# InputChannel.net
KiCad netlist of a schematic drawn in EAGLE
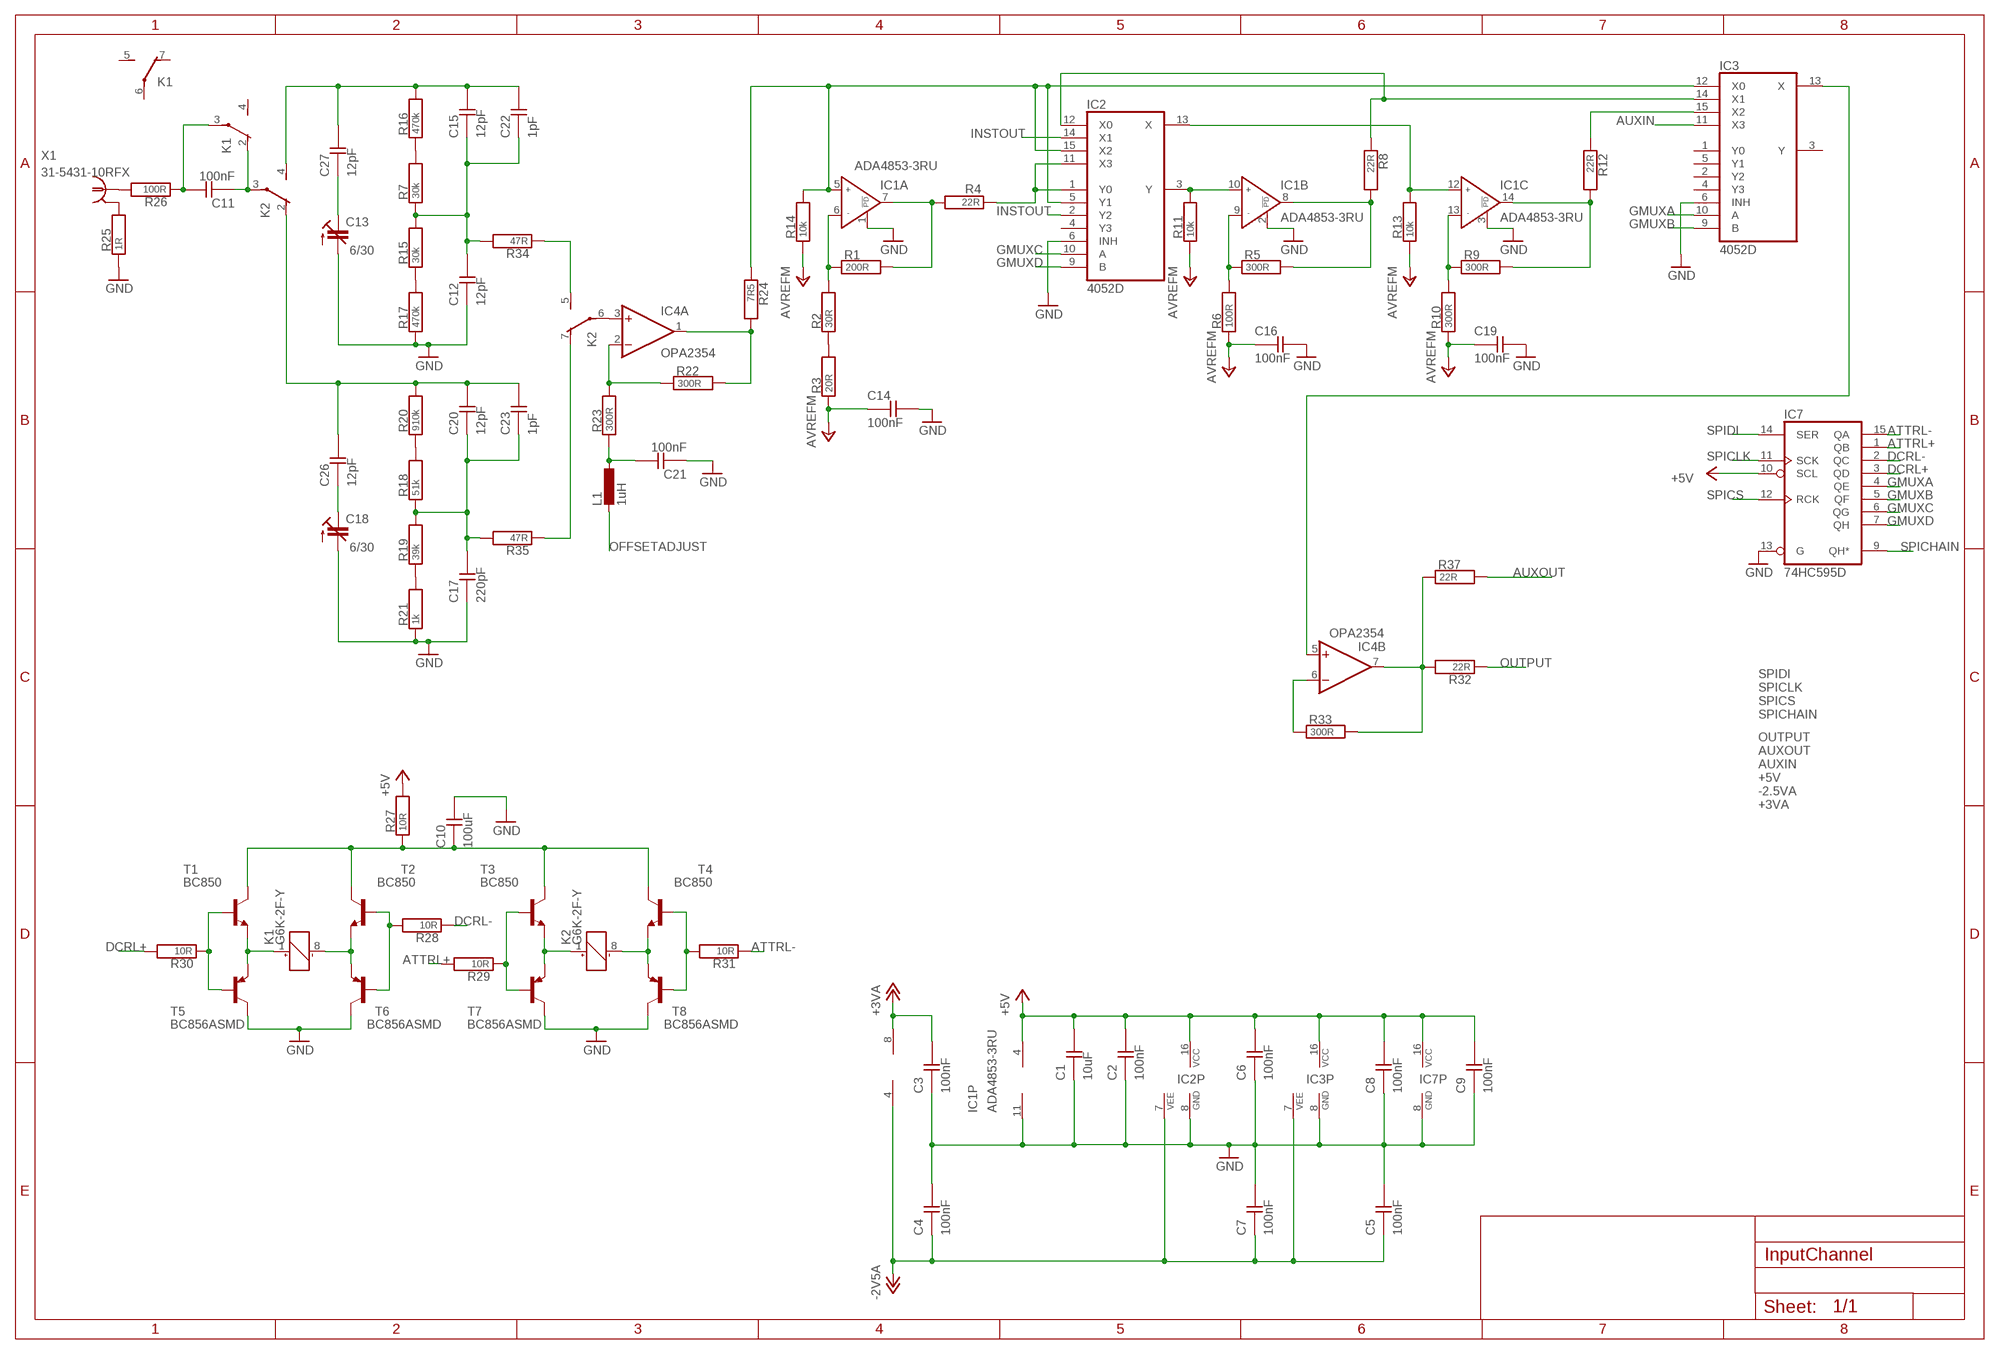
[diagram p0: schematic, sheet 1]

(export (version "E")
  (design (tool "Eeschema 10.0.6"))
  (components
    (comp (ref "C1")
      (value "10uF")
      (footprint "eagle-import:0603")
      (libsource (lib "eagle-import") (part "CAPC0603"))
    )
    (comp (ref "C2")
      (value "100nF")
      (footprint "eagle-import:0603")
      (libsource (lib "eagle-import") (part "CAPC0603"))
    )
    (comp (ref "C3")
      (value "100nF")
      (footprint "eagle-import:0603")
      (libsource (lib "eagle-import") (part "CAPC0603"))
    )
    (comp (ref "C4")
      (value "100nF")
      (footprint "eagle-import:0402")
      (libsource (lib "eagle-import") (part "CAPC0402"))
    )
    (comp (ref "C5")
      (value "100nF")
      (footprint "eagle-import:0603")
      (libsource (lib "eagle-import") (part "CAPC0603"))
    )
    (comp (ref "C6")
      (value "100nF")
      (footprint "eagle-import:0603")
      (libsource (lib "eagle-import") (part "CAPC0603"))
    )
    (comp (ref "C7")
      (value "100nF")
      (footprint "eagle-import:0603")
      (libsource (lib "eagle-import") (part "CAPC0603"))
    )
    (comp (ref "C8")
      (value "100nF")
      (footprint "eagle-import:0603")
      (libsource (lib "eagle-import") (part "CAPC0603"))
    )
    (comp (ref "C9")
      (value "100nF")
      (footprint "eagle-import:0603")
      (libsource (lib "eagle-import") (part "CAPC0603"))
    )
    (comp (ref "C10")
      (value "100uF")
      (footprint "eagle-import:1206")
      (libsource (lib "eagle-import") (part "CAPC1206"))
    )
    (comp (ref "C11")
      (value "100nF")
      (footprint "eagle-import:0603")
      (libsource (lib "eagle-import") (part "CAPC0603"))
    )
    (comp (ref "C12")
      (value "12pF")
      (footprint "eagle-import:0603")
      (libsource (lib "eagle-import") (part "CAPC0603"))
    )
    (comp (ref "C13")
      (value "6/30")
      (footprint "eagle-import:CTRIMTZBX4")
      (libsource (lib "eagle-import") (part "C-TRIMMTZBX4"))
    )
    (comp (ref "C14")
      (value "100nF")
      (footprint "eagle-import:0402")
      (libsource (lib "eagle-import") (part "CAPC0402"))
    )
    (comp (ref "C15")
      (value "12pF")
      (footprint "eagle-import:0603")
      (libsource (lib "eagle-import") (part "CAPC0603"))
    )
    (comp (ref "C16")
      (value "100nF")
      (footprint "eagle-import:0402")
      (libsource (lib "eagle-import") (part "CAPC0402"))
    )
    (comp (ref "C17")
      (value "220pF")
      (footprint "eagle-import:0603")
      (libsource (lib "eagle-import") (part "CAPC0603"))
    )
    (comp (ref "C18")
      (value "6/30")
      (footprint "eagle-import:CTRIMTZBX4")
      (libsource (lib "eagle-import") (part "C-TRIMMTZBX4"))
    )
    (comp (ref "C19")
      (value "100nF")
      (footprint "eagle-import:0402")
      (libsource (lib "eagle-import") (part "CAPC0402"))
    )
    (comp (ref "C20")
      (value "12pF")
      (footprint "eagle-import:0603")
      (libsource (lib "eagle-import") (part "CAPC0603"))
    )
    (comp (ref "C21")
      (value "100nF")
      (footprint "eagle-import:0402")
      (libsource (lib "eagle-import") (part "CAPC0402"))
    )
    (comp (ref "C22")
      (value "1pF")
      (footprint "eagle-import:0603")
      (libsource (lib "eagle-import") (part "CAPC0603"))
    )
    (comp (ref "C23")
      (value "1pF")
      (footprint "eagle-import:0603")
      (libsource (lib "eagle-import") (part "CAPC0603"))
    )
    (comp (ref "C26")
      (value "12pF")
      (footprint "eagle-import:0603")
      (libsource (lib "eagle-import") (part "CAPC0603"))
    )
    (comp (ref "C27")
      (value "12pF")
      (footprint "eagle-import:0603")
      (libsource (lib "eagle-import") (part "CAPC0603"))
    )
    (comp (ref "IC1")
      (value "ADA4853-3RU")
      (footprint "eagle-import:SO14")
      (libsource (lib "eagle-import") (part "ADA4853-3RU"))
    )
    (comp (ref "IC2")
      (value "4052D")
      (footprint "eagle-import:SO16")
      (libsource (lib "eagle-import") (part "4052D"))
    )
    (comp (ref "IC3")
      (value "4052D")
      (footprint "eagle-import:SO16")
      (libsource (lib "eagle-import") (part "4052D"))
    )
    (comp (ref "IC4")
      (value "OPA2354")
      (footprint "eagle-import:MSOP08")
      (libsource (lib "eagle-import") (part "AD8682RM"))
    )
    (comp (ref "IC7")
      (value "74HC595D")
      (footprint "eagle-import:SO16")
      (libsource (lib "eagle-import") (part "74595DHC"))
    )
    (comp (ref "K1")
      (value "G6K-2F-Y")
      (footprint "eagle-import:G6K-2F-Y")
      (fields (field (name "MF") "OMRON COMPONENTS USA") (field (name "MPN") "G6K-2F-Y DC3"))
      (libsource (lib "eagle-import") (part "G6K-2F-Y"))
    )
    (comp (ref "K2")
      (value "G6K-2F-Y")
      (footprint "eagle-import:G6K-2F-Y")
      (fields (field (name "MF") "OMRON COMPONENTS USA") (field (name "MPN") "G6K-2F-Y DC3"))
      (libsource (lib "eagle-import") (part "G6K-2F-Y"))
    )
    (comp (ref "L1")
      (value "1uH")
      (footprint "eagle-import:L3216C")
      (libsource (lib "eagle-import") (part "L-EUL3216C"))
    )
    (comp (ref "R1")
      (value "200R")
      (footprint "eagle-import:0603")
      (libsource (lib "eagle-import") (part "RESR0603"))
    )
    (comp (ref "R2")
      (value "30R")
      (footprint "eagle-import:0603")
      (libsource (lib "eagle-import") (part "RESR0603"))
    )
    (comp (ref "R3")
      (value "20R")
      (footprint "eagle-import:0603")
      (libsource (lib "eagle-import") (part "RESR0603"))
    )
    (comp (ref "R4")
      (value "22R")
      (footprint "eagle-import:0603")
      (libsource (lib "eagle-import") (part "RESR0603"))
    )
    (comp (ref "R5")
      (value "300R")
      (footprint "eagle-import:0603")
      (libsource (lib "eagle-import") (part "RESR0603"))
    )
    (comp (ref "R6")
      (value "100R")
      (footprint "eagle-import:0603")
      (libsource (lib "eagle-import") (part "RESR0603"))
    )
    (comp (ref "R7")
      (value "30k")
      (footprint "eagle-import:0603")
      (libsource (lib "eagle-import") (part "RESR0603"))
    )
    (comp (ref "R8")
      (value "22R")
      (footprint "eagle-import:0603")
      (libsource (lib "eagle-import") (part "RESR0603"))
    )
    (comp (ref "R9")
      (value "300R")
      (footprint "eagle-import:0603")
      (libsource (lib "eagle-import") (part "RESR0603"))
    )
    (comp (ref "R10")
      (value "300R")
      (footprint "eagle-import:0603")
      (libsource (lib "eagle-import") (part "RESR0603"))
    )
    (comp (ref "R11")
      (value "10k")
      (footprint "eagle-import:0603")
      (libsource (lib "eagle-import") (part "RESR0603"))
    )
    (comp (ref "R12")
      (value "22R")
      (footprint "eagle-import:0603")
      (libsource (lib "eagle-import") (part "RESR0603"))
    )
    (comp (ref "R13")
      (value "10k")
      (footprint "eagle-import:0603")
      (libsource (lib "eagle-import") (part "RESR0603"))
    )
    (comp (ref "R14")
      (value "10k")
      (footprint "eagle-import:0603")
      (libsource (lib "eagle-import") (part "RESR0603"))
    )
    (comp (ref "R15")
      (value "30k")
      (footprint "eagle-import:0603")
      (libsource (lib "eagle-import") (part "RESR0603"))
    )
    (comp (ref "R16")
      (value "470k")
      (footprint "eagle-import:0603")
      (libsource (lib "eagle-import") (part "RESR0603"))
    )
    (comp (ref "R17")
      (value "470k")
      (footprint "eagle-import:0603")
      (libsource (lib "eagle-import") (part "RESR0603"))
    )
    (comp (ref "R18")
      (value "51k")
      (footprint "eagle-import:0603")
      (libsource (lib "eagle-import") (part "RESR0603"))
    )
    (comp (ref "R19")
      (value "39k")
      (footprint "eagle-import:0603")
      (libsource (lib "eagle-import") (part "RESR0603"))
    )
    (comp (ref "R20")
      (value "910k")
      (footprint "eagle-import:0603")
      (libsource (lib "eagle-import") (part "RESR0603"))
    )
    (comp (ref "R21")
      (value "1k")
      (footprint "eagle-import:0603")
      (libsource (lib "eagle-import") (part "RESR0603"))
    )
    (comp (ref "R22")
      (value "300R")
      (footprint "eagle-import:0603")
      (libsource (lib "eagle-import") (part "RESR0603"))
    )
    (comp (ref "R23")
      (value "300R")
      (footprint "eagle-import:0603")
      (libsource (lib "eagle-import") (part "RESR0603"))
    )
    (comp (ref "R24")
      (value "7R5")
      (footprint "eagle-import:0603")
      (libsource (lib "eagle-import") (part "RESR0603"))
    )
    (comp (ref "R25")
      (value "1R")
      (footprint "eagle-import:0603")
      (libsource (lib "eagle-import") (part "RESR0603"))
    )
    (comp (ref "R26")
      (value "100R")
      (footprint "eagle-import:0603")
      (libsource (lib "eagle-import") (part "RESR0603"))
    )
    (comp (ref "R27")
      (value "10R")
      (footprint "eagle-import:0603")
      (libsource (lib "eagle-import") (part "RESR0603"))
    )
    (comp (ref "R28")
      (value "10R")
      (footprint "eagle-import:0603")
      (libsource (lib "eagle-import") (part "RESR0603"))
    )
    (comp (ref "R29")
      (value "10R")
      (footprint "eagle-import:0603")
      (libsource (lib "eagle-import") (part "RESR0603"))
    )
    (comp (ref "R30")
      (value "10R")
      (footprint "eagle-import:0603")
      (libsource (lib "eagle-import") (part "RESR0603"))
    )
    (comp (ref "R31")
      (value "10R")
      (footprint "eagle-import:0603")
      (libsource (lib "eagle-import") (part "RESR0603"))
    )
    (comp (ref "R32")
      (value "22R")
      (footprint "eagle-import:0603")
      (libsource (lib "eagle-import") (part "RESR0603"))
    )
    (comp (ref "R33")
      (value "300R")
      (footprint "eagle-import:0603")
      (libsource (lib "eagle-import") (part "RESR0603"))
    )
    (comp (ref "R34")
      (value "47R")
      (footprint "eagle-import:0603")
      (libsource (lib "eagle-import") (part "RESR0603"))
    )
    (comp (ref "R35")
      (value "47R")
      (footprint "eagle-import:0603")
      (libsource (lib "eagle-import") (part "RESR0603"))
    )
    (comp (ref "R37")
      (value "22R")
      (footprint "eagle-import:0603")
      (libsource (lib "eagle-import") (part "RESR0603"))
    )
    (comp (ref "T1")
      (value "BC850")
      (footprint "eagle-import:SOT23")
      (libsource (lib "eagle-import") (part "BC850"))
    )
    (comp (ref "T2")
      (value "BC850")
      (footprint "eagle-import:SOT23")
      (libsource (lib "eagle-import") (part "BC850"))
    )
    (comp (ref "T3")
      (value "BC850")
      (footprint "eagle-import:SOT23")
      (libsource (lib "eagle-import") (part "BC850"))
    )
    (comp (ref "T4")
      (value "BC850")
      (footprint "eagle-import:SOT23")
      (libsource (lib "eagle-import") (part "BC850"))
    )
    (comp (ref "T5")
      (value "BC856ASMD")
      (footprint "eagle-import:SOT23-BEC")
      (libsource (lib "eagle-import") (part "BC856SMDA"))
    )
    (comp (ref "T6")
      (value "BC856ASMD")
      (footprint "eagle-import:SOT23-BEC")
      (libsource (lib "eagle-import") (part "BC856SMDA"))
    )
    (comp (ref "T7")
      (value "BC856ASMD")
      (footprint "eagle-import:SOT23-BEC")
      (libsource (lib "eagle-import") (part "BC856SMDA"))
    )
    (comp (ref "T8")
      (value "BC856ASMD")
      (footprint "eagle-import:SOT23-BEC")
      (libsource (lib "eagle-import") (part "BC856SMDA"))
    )
    (comp (ref "X1")
      (value "31-5431-10RFX")
      (footprint "eagle-import:AMP_227161")
      (libsource (lib "eagle-import") (part "?227161-8"))
    )
  )
  (nets
    (net (code "1") (name "+3VA") (class "Default")
      (node (ref "C3") (pin "2") (pinfunction "2_2") (pintype "passive"))
      (node (ref "IC4") (pin "8") (pinfunction "V+_8") (pintype "power_in"))
    )
    (net (code "2") (name "+5V") (class "Default")
      (node (ref "C1") (pin "2") (pinfunction "2_2") (pintype "passive"))
      (node (ref "C2") (pin "2") (pinfunction "2_2") (pintype "passive"))
      (node (ref "C6") (pin "2") (pinfunction "2_2") (pintype "passive"))
      (node (ref "C8") (pin "2") (pinfunction "2_2") (pintype "passive"))
      (node (ref "C9") (pin "2") (pinfunction "2_2") (pintype "passive"))
      (node (ref "IC1") (pin "4") (pinfunction "V+_4") (pintype "power_in"))
      (node (ref "IC2") (pin "16") (pinfunction "VCC_16") (pintype "power_in"))
      (node (ref "IC3") (pin "16") (pinfunction "VCC_16") (pintype "power_in"))
      (node (ref "IC7") (pin "10") (pinfunction "SCL_10") (pintype "input"))
      (node (ref "IC7") (pin "16") (pinfunction "VCC_16") (pintype "power_in"))
      (node (ref "R27") (pin "2") (pinfunction "P$2_2") (pintype "bidirectional"))
    )
    (net (code "3") (name "-2V5A") (class "Default")
      (node (ref "C4") (pin "1") (pinfunction "1_1") (pintype "passive"))
      (node (ref "C5") (pin "1") (pinfunction "1_1") (pintype "passive"))
      (node (ref "C7") (pin "1") (pinfunction "1_1") (pintype "passive"))
      (node (ref "IC2") (pin "7") (pinfunction "VEE_7") (pintype "power_in"))
      (node (ref "IC3") (pin "7") (pinfunction "VEE_7") (pintype "power_in"))
      (node (ref "IC4") (pin "4") (pinfunction "V-_4") (pintype "power_in"))
    )
    (net (code "4") (name "/ATTRL+") (class "Default")
      (node (ref "IC7") (pin "1") (pinfunction "QB_1") (pintype "tri_state"))
      (node (ref "R29") (pin "2") (pinfunction "P$2_2") (pintype "bidirectional"))
    )
    (net (code "5") (name "/ATTRL-") (class "Default")
      (node (ref "IC7") (pin "15") (pinfunction "QA_15") (pintype "tri_state"))
      (node (ref "R31") (pin "1") (pinfunction "P$1_1") (pintype "bidirectional"))
    )
    (net (code "6") (name "/AUXIN") (class "Default")
      (node (ref "IC3") (pin "11") (pinfunction "X3_11") (pintype "bidirectional"))
    )
    (net (code "7") (name "/AUXOUT") (class "Default")
      (node (ref "R37") (pin "2") (pinfunction "P$2_2") (pintype "bidirectional"))
    )
    (net (code "8") (name "/DCRL+") (class "Default")
      (node (ref "IC7") (pin "3") (pinfunction "QD_3") (pintype "tri_state"))
      (node (ref "R30") (pin "2") (pinfunction "P$2_2") (pintype "bidirectional"))
    )
    (net (code "9") (name "/DCRL-") (class "Default")
      (node (ref "IC7") (pin "2") (pinfunction "QC_2") (pintype "tri_state"))
      (node (ref "R28") (pin "1") (pinfunction "P$1_1") (pintype "bidirectional"))
    )
    (net (code "10") (name "/GMUXA") (class "Default")
      (node (ref "IC3") (pin "10") (pinfunction "A_10") (pintype "input"))
      (node (ref "IC7") (pin "4") (pinfunction "QE_4") (pintype "tri_state"))
    )
    (net (code "11") (name "/GMUXB") (class "Default")
      (node (ref "IC3") (pin "9") (pinfunction "B_9") (pintype "input"))
      (node (ref "IC7") (pin "5") (pinfunction "QF_5") (pintype "tri_state"))
    )
    (net (code "12") (name "/GMUXC") (class "Default")
      (node (ref "IC2") (pin "10") (pinfunction "A_10") (pintype "input"))
      (node (ref "IC7") (pin "6") (pinfunction "QG_6") (pintype "tri_state"))
    )
    (net (code "13") (name "/GMUXD") (class "Default")
      (node (ref "IC2") (pin "9") (pinfunction "B_9") (pintype "input"))
      (node (ref "IC7") (pin "7") (pinfunction "QH_7") (pintype "tri_state"))
    )
    (net (code "14") (name "/INSTOUT") (class "Default")
      (node (ref "IC2") (pin "14") (pinfunction "X1_14") (pintype "bidirectional"))
      (node (ref "IC2") (pin "2") (pinfunction "Y2_2") (pintype "bidirectional"))
    )
    (net (code "15") (name "/OFFSETADJUST") (class "Default")
      (node (ref "L1") (pin "2") (pinfunction "2_2") (pintype "passive"))
    )
    (net (code "16") (name "/OUTPUT") (class "Default")
      (node (ref "R32") (pin "1") (pinfunction "P$1_1") (pintype "bidirectional"))
    )
    (net (code "17") (name "/SPICHAIN") (class "Default")
      (node (ref "IC7") (pin "9") (pinfunction "QH*_9") (pintype "tri_state"))
    )
    (net (code "18") (name "/SPICLK") (class "Default")
      (node (ref "IC7") (pin "11") (pinfunction "SCK_11") (pintype "input"))
    )
    (net (code "19") (name "/SPICS") (class "Default")
      (node (ref "IC7") (pin "12") (pinfunction "RCK_12") (pintype "input"))
    )
    (net (code "20") (name "/SPIDI") (class "Default")
      (node (ref "IC7") (pin "14") (pinfunction "SER_14") (pintype "input"))
    )
    (net (code "21") (name "AVREFM") (class "Default")
      (node (ref "C14") (pin "1") (pinfunction "1_1") (pintype "passive"))
      (node (ref "C16") (pin "1") (pinfunction "1_1") (pintype "passive"))
      (node (ref "C19") (pin "1") (pinfunction "1_1") (pintype "passive"))
      (node (ref "R10") (pin "1") (pinfunction "P$1_1") (pintype "bidirectional"))
      (node (ref "R11") (pin "1") (pinfunction "P$1_1") (pintype "bidirectional"))
      (node (ref "R13") (pin "1") (pinfunction "P$1_1") (pintype "bidirectional"))
      (node (ref "R14") (pin "1") (pinfunction "P$1_1") (pintype "bidirectional"))
      (node (ref "R3") (pin "1") (pinfunction "P$1_1") (pintype "bidirectional"))
      (node (ref "R6") (pin "1") (pinfunction "P$1_1") (pintype "bidirectional"))
    )
    (net (code "22") (name "GND") (class "Default")
      (node (ref "C1") (pin "1") (pinfunction "1_1") (pintype "passive"))
      (node (ref "C10") (pin "2") (pinfunction "2_2") (pintype "passive"))
      (node (ref "C12") (pin "1") (pinfunction "1_1") (pintype "passive"))
      (node (ref "C13") (pin "2") (pinfunction "A_2") (pintype "passive"))
      (node (ref "C14") (pin "2") (pinfunction "2_2") (pintype "passive"))
      (node (ref "C16") (pin "2") (pinfunction "2_2") (pintype "passive"))
      (node (ref "C17") (pin "1") (pinfunction "1_1") (pintype "passive"))
      (node (ref "C18") (pin "2") (pinfunction "A_2") (pintype "passive"))
      (node (ref "C19") (pin "2") (pinfunction "2_2") (pintype "passive"))
      (node (ref "C2") (pin "1") (pinfunction "1_1") (pintype "passive"))
      (node (ref "C21") (pin "1") (pinfunction "1_1") (pintype "passive"))
      (node (ref "C3") (pin "1") (pinfunction "1_1") (pintype "passive"))
      (node (ref "C4") (pin "2") (pinfunction "2_2") (pintype "passive"))
      (node (ref "C5") (pin "2") (pinfunction "2_2") (pintype "passive"))
      (node (ref "C6") (pin "1") (pinfunction "1_1") (pintype "passive"))
      (node (ref "C7") (pin "2") (pinfunction "2_2") (pintype "passive"))
      (node (ref "C8") (pin "1") (pinfunction "1_1") (pintype "passive"))
      (node (ref "C9") (pin "1") (pinfunction "1_1") (pintype "passive"))
      (node (ref "IC1") (pin "1") (pinfunction "~{POWERDOWN}_1") (pintype "passive"))
      (node (ref "IC1") (pin "11") (pinfunction "V-_11") (pintype "power_in"))
      (node (ref "IC1") (pin "2") (pinfunction "~{POWERDOWN}_2") (pintype "passive"))
      (node (ref "IC1") (pin "3") (pinfunction "~{POWERDOWN}_3") (pintype "passive"))
      (node (ref "IC2") (pin "6") (pinfunction "INH_6") (pintype "input"))
      (node (ref "IC2") (pin "8") (pinfunction "GND_8") (pintype "power_in"))
      (node (ref "IC3") (pin "6") (pinfunction "INH_6") (pintype "input"))
      (node (ref "IC3") (pin "8") (pinfunction "GND_8") (pintype "power_in"))
      (node (ref "IC7") (pin "13") (pinfunction "G_13") (pintype "input"))
      (node (ref "IC7") (pin "8") (pinfunction "GND_8") (pintype "power_in"))
      (node (ref "R17") (pin "1") (pinfunction "P$1_1") (pintype "bidirectional"))
      (node (ref "R21") (pin "1") (pinfunction "P$1_1") (pintype "bidirectional"))
      (node (ref "R25") (pin "1") (pinfunction "P$1_1") (pintype "bidirectional"))
      (node (ref "T5") (pin "C") (pinfunction "C_C") (pintype "passive"))
      (node (ref "T6") (pin "C") (pinfunction "C_C") (pintype "passive"))
      (node (ref "T7") (pin "C") (pinfunction "C_C") (pintype "passive"))
      (node (ref "T8") (pin "C") (pinfunction "C_C") (pintype "passive"))
    )
    (net (code "23") (name "Net-(C13-E)") (class "Default")
      (node (ref "C13") (pin "1") (pinfunction "E_1") (pintype "passive"))
      (node (ref "C27") (pin "1") (pinfunction "1_1") (pintype "passive"))
    )
    (net (code "24") (name "Net-(C18-E)") (class "Default")
      (node (ref "C18") (pin "1") (pinfunction "E_1") (pintype "passive"))
      (node (ref "C26") (pin "1") (pinfunction "1_1") (pintype "passive"))
    )
    (net (code "25") (name "Net-(IC1A-IN+)") (class "Default")
      (node (ref "IC1") (pin "5") (pinfunction "IN+_5") (pintype "input"))
      (node (ref "IC2") (pin "15") (pinfunction "X2_15") (pintype "bidirectional"))
      (node (ref "IC2") (pin "5") (pinfunction "Y1_5") (pintype "bidirectional"))
      (node (ref "IC3") (pin "12") (pinfunction "X0_12") (pintype "bidirectional"))
      (node (ref "R14") (pin "2") (pinfunction "P$2_2") (pintype "bidirectional"))
      (node (ref "R24") (pin "1") (pinfunction "P$1_1") (pintype "bidirectional"))
    )
    (net (code "26") (name "Net-(IC1A-IN-)") (class "Default")
      (node (ref "IC1") (pin "6") (pinfunction "IN-_6") (pintype "input"))
      (node (ref "R1") (pin "1") (pinfunction "P$1_1") (pintype "bidirectional"))
      (node (ref "R2") (pin "2") (pinfunction "P$2_2") (pintype "bidirectional"))
    )
    (net (code "27") (name "Net-(IC1A-OUT)") (class "Default")
      (node (ref "IC1") (pin "7") (pinfunction "OUT_7") (pintype "output"))
      (node (ref "R1") (pin "2") (pinfunction "P$2_2") (pintype "bidirectional"))
      (node (ref "R4") (pin "2") (pinfunction "P$2_2") (pintype "bidirectional"))
    )
    (net (code "28") (name "Net-(IC1B-IN+)") (class "Default")
      (node (ref "IC1") (pin "10") (pinfunction "IN+_10") (pintype "input"))
      (node (ref "IC2") (pin "3") (pinfunction "Y_3") (pintype "bidirectional"))
      (node (ref "R11") (pin "2") (pinfunction "P$2_2") (pintype "bidirectional"))
    )
    (net (code "29") (name "Net-(IC1B-IN-)") (class "Default")
      (node (ref "IC1") (pin "9") (pinfunction "IN-_9") (pintype "input"))
      (node (ref "R5") (pin "1") (pinfunction "P$1_1") (pintype "bidirectional"))
      (node (ref "R6") (pin "2") (pinfunction "P$2_2") (pintype "bidirectional"))
    )
    (net (code "30") (name "Net-(IC1B-OUT)") (class "Default")
      (node (ref "IC1") (pin "8") (pinfunction "OUT_8") (pintype "output"))
      (node (ref "R5") (pin "2") (pinfunction "P$2_2") (pintype "bidirectional"))
      (node (ref "R8") (pin "2") (pinfunction "P$2_2") (pintype "bidirectional"))
    )
    (net (code "31") (name "Net-(IC1C-IN+)") (class "Default")
      (node (ref "IC1") (pin "12") (pinfunction "IN+_12") (pintype "input"))
      (node (ref "IC2") (pin "13") (pinfunction "X_13") (pintype "bidirectional"))
      (node (ref "R13") (pin "2") (pinfunction "P$2_2") (pintype "bidirectional"))
    )
    (net (code "32") (name "Net-(IC1C-IN-)") (class "Default")
      (node (ref "IC1") (pin "13") (pinfunction "IN-_13") (pintype "input"))
      (node (ref "R10") (pin "2") (pinfunction "P$2_2") (pintype "bidirectional"))
      (node (ref "R9") (pin "1") (pinfunction "P$1_1") (pintype "bidirectional"))
    )
    (net (code "33") (name "Net-(IC1C-OUT)") (class "Default")
      (node (ref "IC1") (pin "14") (pinfunction "OUT_14") (pintype "output"))
      (node (ref "R12") (pin "2") (pinfunction "P$2_2") (pintype "bidirectional"))
      (node (ref "R9") (pin "2") (pinfunction "P$2_2") (pintype "bidirectional"))
    )
    (net (code "34") (name "Net-(IC2A-X0)") (class "Default")
      (node (ref "IC2") (pin "12") (pinfunction "X0_12") (pintype "bidirectional"))
      (node (ref "IC3") (pin "14") (pinfunction "X1_14") (pintype "bidirectional"))
      (node (ref "R8") (pin "1") (pinfunction "P$1_1") (pintype "bidirectional"))
    )
    (net (code "35") (name "Net-(IC2A-X3)") (class "Default")
      (node (ref "IC2") (pin "1") (pinfunction "Y0_1") (pintype "bidirectional"))
      (node (ref "IC2") (pin "11") (pinfunction "X3_11") (pintype "bidirectional"))
      (node (ref "R4") (pin "1") (pinfunction "P$1_1") (pintype "bidirectional"))
    )
    (net (code "36") (name "Net-(IC3A-X)") (class "Default")
      (node (ref "IC3") (pin "13") (pinfunction "X_13") (pintype "bidirectional"))
      (node (ref "IC4") (pin "5") (pinfunction "+IN_5") (pintype "input"))
    )
    (net (code "37") (name "Net-(IC3A-X2)") (class "Default")
      (node (ref "IC3") (pin "15") (pinfunction "X2_15") (pintype "bidirectional"))
      (node (ref "R12") (pin "1") (pinfunction "P$1_1") (pintype "bidirectional"))
    )
    (net (code "38") (name "Net-(IC4A-+IN)") (class "Default")
      (node (ref "IC4") (pin "3") (pinfunction "+IN_3") (pintype "input"))
      (node (ref "K2") (pin "6") (pinfunction "P_6") (pintype "passive"))
    )
    (net (code "39") (name "Net-(IC4A--IN)") (class "Default")
      (node (ref "IC4") (pin "2") (pinfunction "-IN_2") (pintype "input"))
      (node (ref "R22") (pin "1") (pinfunction "P$1_1") (pintype "bidirectional"))
      (node (ref "R23") (pin "2") (pinfunction "P$2_2") (pintype "bidirectional"))
    )
    (net (code "40") (name "Net-(IC4A-OUT)") (class "Default")
      (node (ref "IC4") (pin "1") (pinfunction "OUT_1") (pintype "output"))
      (node (ref "R22") (pin "2") (pinfunction "P$2_2") (pintype "bidirectional"))
      (node (ref "R24") (pin "2") (pinfunction "P$2_2") (pintype "bidirectional"))
    )
    (net (code "41") (name "Net-(IC4B--IN)") (class "Default")
      (node (ref "IC4") (pin "6") (pinfunction "-IN_6") (pintype "input"))
      (node (ref "R33") (pin "1") (pinfunction "P$1_1") (pintype "bidirectional"))
    )
    (net (code "42") (name "Net-(IC4B-OUT)") (class "Default")
      (node (ref "IC4") (pin "7") (pinfunction "OUT_7") (pintype "output"))
      (node (ref "R32") (pin "2") (pinfunction "P$2_2") (pintype "bidirectional"))
      (node (ref "R33") (pin "2") (pinfunction "P$2_2") (pintype "bidirectional"))
      (node (ref "R37") (pin "1") (pinfunction "P$1_1") (pintype "bidirectional"))
    )
    (net (code "43") (name "Net-(K1A-+)") (class "Default")
      (node (ref "K1") (pin "1") (pinfunction "+_1") (pintype "passive"))
      (node (ref "T1") (pin "2") (pinfunction "E_2") (pintype "passive"))
      (node (ref "T5") (pin "E") (pinfunction "E_E") (pintype "passive"))
    )
    (net (code "44") (name "Net-(K1A--)") (class "Default")
      (node (ref "K1") (pin "8") (pinfunction "-_8") (pintype "passive"))
      (node (ref "T2") (pin "2") (pinfunction "E_2") (pintype "passive"))
      (node (ref "T6") (pin "E") (pinfunction "E_E") (pintype "passive"))
    )
    (net (code "45") (name "Net-(K1B-O)") (class "Default")
      (node (ref "C11") (pin "1") (pinfunction "1_1") (pintype "passive"))
      (node (ref "K1") (pin "2") (pinfunction "O_2") (pintype "passive"))
      (node (ref "K2") (pin "3") (pinfunction "P_3") (pintype "passive"))
    )
    (net (code "46") (name "Net-(K1B-P)") (class "Default")
      (node (ref "C11") (pin "2") (pinfunction "2_2") (pintype "passive"))
      (node (ref "K1") (pin "3") (pinfunction "P_3") (pintype "passive"))
      (node (ref "R26") (pin "1") (pinfunction "P$1_1") (pintype "bidirectional"))
    )
    (net (code "47") (name "Net-(K2A-+)") (class "Default")
      (node (ref "K2") (pin "1") (pinfunction "+_1") (pintype "passive"))
      (node (ref "T3") (pin "2") (pinfunction "E_2") (pintype "passive"))
      (node (ref "T7") (pin "E") (pinfunction "E_E") (pintype "passive"))
    )
    (net (code "48") (name "Net-(K2A--)") (class "Default")
      (node (ref "K2") (pin "8") (pinfunction "-_8") (pintype "passive"))
      (node (ref "T4") (pin "2") (pinfunction "E_2") (pintype "passive"))
      (node (ref "T8") (pin "E") (pinfunction "E_E") (pintype "passive"))
    )
    (net (code "49") (name "Net-(K2B-O)") (class "Default")
      (node (ref "C20") (pin "2") (pinfunction "2_2") (pintype "passive"))
      (node (ref "C23") (pin "2") (pinfunction "2_2") (pintype "passive"))
      (node (ref "C26") (pin "2") (pinfunction "2_2") (pintype "passive"))
      (node (ref "K2") (pin "2") (pinfunction "O_2") (pintype "passive"))
      (node (ref "R20") (pin "2") (pinfunction "P$2_2") (pintype "bidirectional"))
    )
    (net (code "50") (name "Net-(K2B-S)") (class "Default")
      (node (ref "C15") (pin "2") (pinfunction "2_2") (pintype "passive"))
      (node (ref "C22") (pin "2") (pinfunction "2_2") (pintype "passive"))
      (node (ref "C27") (pin "2") (pinfunction "2_2") (pintype "passive"))
      (node (ref "K2") (pin "4") (pinfunction "S_4") (pintype "passive"))
      (node (ref "R16") (pin "2") (pinfunction "P$2_2") (pintype "bidirectional"))
    )
    (net (code "51") (name "Net-(K2C-O)") (class "Default")
      (node (ref "K2") (pin "7") (pinfunction "O_7") (pintype "passive"))
      (node (ref "R35") (pin "1") (pinfunction "P$1_1") (pintype "bidirectional"))
    )
    (net (code "52") (name "Net-(K2C-S)") (class "Default")
      (node (ref "K2") (pin "5") (pinfunction "S_5") (pintype "passive"))
      (node (ref "R34") (pin "1") (pinfunction "P$1_1") (pintype "bidirectional"))
    )
    (net (code "53") (name "Net-(R2-P$1)") (class "Default")
      (node (ref "R2") (pin "1") (pinfunction "P$1_1") (pintype "bidirectional"))
      (node (ref "R3") (pin "2") (pinfunction "P$2_2") (pintype "bidirectional"))
    )
    (net (code "54") (name "Net-(R15-P$1)") (class "Default")
      (node (ref "R15") (pin "1") (pinfunction "P$1_1") (pintype "bidirectional"))
      (node (ref "R17") (pin "2") (pinfunction "P$2_2") (pintype "bidirectional"))
    )
    (net (code "55") (name "Net-(R15-P$2)") (class "Default")
      (node (ref "C12") (pin "2") (pinfunction "2_2") (pintype "passive"))
      (node (ref "C15") (pin "1") (pinfunction "1_1") (pintype "passive"))
      (node (ref "C22") (pin "1") (pinfunction "1_1") (pintype "passive"))
      (node (ref "R15") (pin "2") (pinfunction "P$2_2") (pintype "bidirectional"))
      (node (ref "R34") (pin "2") (pinfunction "P$2_2") (pintype "bidirectional"))
      (node (ref "R7") (pin "1") (pinfunction "P$1_1") (pintype "bidirectional"))
    )
    (net (code "56") (name "Net-(R16-P$1)") (class "Default")
      (node (ref "R16") (pin "1") (pinfunction "P$1_1") (pintype "bidirectional"))
      (node (ref "R7") (pin "2") (pinfunction "P$2_2") (pintype "bidirectional"))
    )
    (net (code "57") (name "Net-(R18-P$1)") (class "Default")
      (node (ref "C17") (pin "2") (pinfunction "2_2") (pintype "passive"))
      (node (ref "C20") (pin "1") (pinfunction "1_1") (pintype "passive"))
      (node (ref "C23") (pin "1") (pinfunction "1_1") (pintype "passive"))
      (node (ref "R18") (pin "1") (pinfunction "P$1_1") (pintype "bidirectional"))
      (node (ref "R19") (pin "2") (pinfunction "P$2_2") (pintype "bidirectional"))
      (node (ref "R35") (pin "2") (pinfunction "P$2_2") (pintype "bidirectional"))
    )
    (net (code "58") (name "Net-(R18-P$2)") (class "Default")
      (node (ref "R18") (pin "2") (pinfunction "P$2_2") (pintype "bidirectional"))
      (node (ref "R20") (pin "1") (pinfunction "P$1_1") (pintype "bidirectional"))
    )
    (net (code "59") (name "Net-(R19-P$1)") (class "Default")
      (node (ref "R19") (pin "1") (pinfunction "P$1_1") (pintype "bidirectional"))
      (node (ref "R21") (pin "2") (pinfunction "P$2_2") (pintype "bidirectional"))
    )
    (net (code "60") (name "Net-(R23-P$1)") (class "Default")
      (node (ref "C21") (pin "2") (pinfunction "2_2") (pintype "passive"))
      (node (ref "L1") (pin "1") (pinfunction "1_1") (pintype "passive"))
      (node (ref "R23") (pin "1") (pinfunction "P$1_1") (pintype "bidirectional"))
    )
    (net (code "61") (name "Net-(R25-P$2)") (class "Default")
      (node (ref "R25") (pin "2") (pinfunction "P$2_2") (pintype "bidirectional"))
      (node (ref "X1") (pin "2") (pinfunction "2_2") (pintype "passive"))
    )
    (net (code "62") (name "Net-(R26-P$2)") (class "Default")
      (node (ref "R26") (pin "2") (pinfunction "P$2_2") (pintype "bidirectional"))
      (node (ref "X1") (pin "1") (pinfunction "1_1") (pintype "passive"))
    )
    (net (code "63") (name "Net-(R27-P$1)") (class "Default")
      (node (ref "C10") (pin "1") (pinfunction "1_1") (pintype "passive"))
      (node (ref "R27") (pin "1") (pinfunction "P$1_1") (pintype "bidirectional"))
      (node (ref "T1") (pin "3") (pinfunction "C_3") (pintype "passive"))
      (node (ref "T2") (pin "3") (pinfunction "C_3") (pintype "passive"))
      (node (ref "T3") (pin "3") (pinfunction "C_3") (pintype "passive"))
      (node (ref "T4") (pin "3") (pinfunction "C_3") (pintype "passive"))
    )
    (net (code "64") (name "Net-(R28-P$2)") (class "Default")
      (node (ref "R28") (pin "2") (pinfunction "P$2_2") (pintype "bidirectional"))
      (node (ref "T2") (pin "1") (pinfunction "B_1") (pintype "passive"))
      (node (ref "T6") (pin "B") (pinfunction "B_B") (pintype "passive"))
    )
    (net (code "65") (name "Net-(R29-P$1)") (class "Default")
      (node (ref "R29") (pin "1") (pinfunction "P$1_1") (pintype "bidirectional"))
      (node (ref "T3") (pin "1") (pinfunction "B_1") (pintype "passive"))
      (node (ref "T7") (pin "B") (pinfunction "B_B") (pintype "passive"))
    )
    (net (code "66") (name "Net-(R30-P$1)") (class "Default")
      (node (ref "R30") (pin "1") (pinfunction "P$1_1") (pintype "bidirectional"))
      (node (ref "T1") (pin "1") (pinfunction "B_1") (pintype "passive"))
      (node (ref "T5") (pin "B") (pinfunction "B_B") (pintype "passive"))
    )
    (net (code "67") (name "Net-(R31-P$2)") (class "Default")
      (node (ref "R31") (pin "2") (pinfunction "P$2_2") (pintype "bidirectional"))
      (node (ref "T4") (pin "1") (pinfunction "B_1") (pintype "passive"))
      (node (ref "T8") (pin "B") (pinfunction "B_B") (pintype "passive"))
    )
    (net (code "68") (name "unconnected-(IC2A-Y3-Pad4)") (class "Default")
      (node (ref "IC2") (pin "4") (pinfunction "Y3_4") (pintype "bidirectional"))
    )
    (net (code "69") (name "unconnected-(IC3A-Y-Pad3)") (class "Default")
      (node (ref "IC3") (pin "3") (pinfunction "Y_3") (pintype "bidirectional"))
    )
    (net (code "70") (name "unconnected-(IC3A-Y0-Pad1)") (class "Default")
      (node (ref "IC3") (pin "1") (pinfunction "Y0_1") (pintype "bidirectional"))
    )
    (net (code "71") (name "unconnected-(IC3A-Y1-Pad5)") (class "Default")
      (node (ref "IC3") (pin "5") (pinfunction "Y1_5") (pintype "bidirectional"))
    )
    (net (code "72") (name "unconnected-(IC3A-Y2-Pad2)") (class "Default")
      (node (ref "IC3") (pin "2") (pinfunction "Y2_2") (pintype "bidirectional"))
    )
    (net (code "73") (name "unconnected-(IC3A-Y3-Pad4)") (class "Default")
      (node (ref "IC3") (pin "4") (pinfunction "Y3_4") (pintype "bidirectional"))
    )
    (net (code "74") (name "unconnected-(K1B-S-Pad4)") (class "Default")
      (node (ref "K1") (pin "4") (pinfunction "S_4") (pintype "passive"))
    )
    (net (code "75") (name "unconnected-(K1C-O-Pad7)") (class "Default")
      (node (ref "K1") (pin "7") (pinfunction "O_7") (pintype "passive"))
    )
    (net (code "76") (name "unconnected-(K1C-P-Pad6)") (class "Default")
      (node (ref "K1") (pin "6") (pinfunction "P_6") (pintype "passive"))
    )
    (net (code "77") (name "unconnected-(K1C-S-Pad5)") (class "Default")
      (node (ref "K1") (pin "5") (pinfunction "S_5") (pintype "passive"))
    )
  )
)
